# main.net
KiCad netlist of a schematic drawn in EAGLE
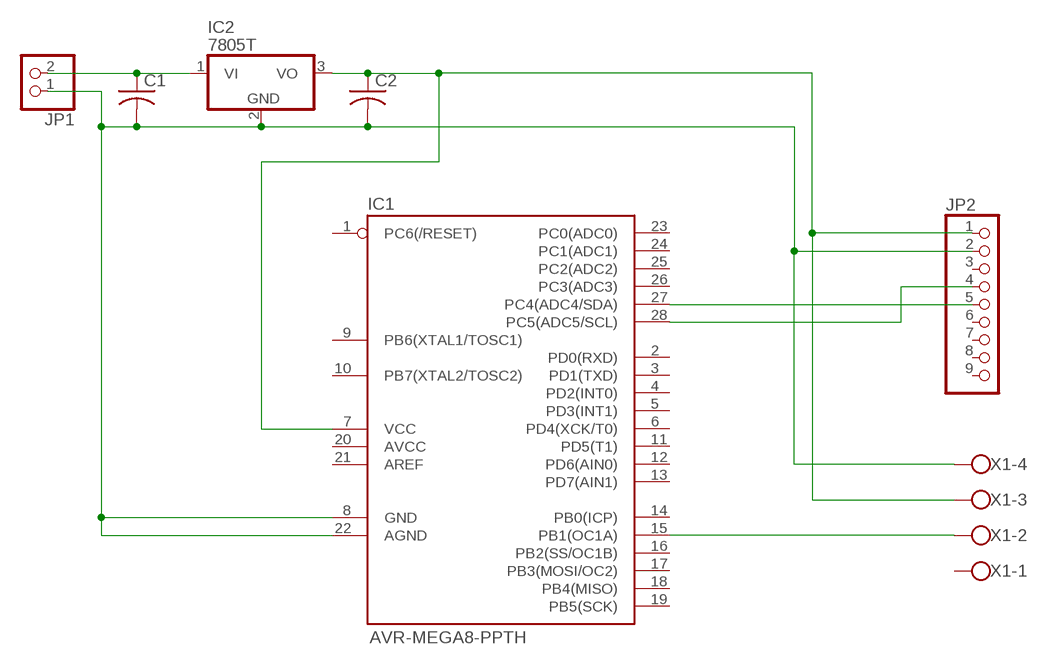
[diagram p0: schematic, sheet 1]

(export (version "E")
  (design (tool "Eeschema 10.0.6"))
  (components
    (comp (ref "C1")
      (value "C-US050-075X075")
      (footprint "eagle-import:C050-075X075")
      (libsource (lib "eagle-import") (part "C-US050-075X075"))
    )
    (comp (ref "C2")
      (value "C-US025-050X050")
      (footprint "eagle-import:C025-050X050")
      (libsource (lib "eagle-import") (part "C-US025-050X050"))
    )
    (comp (ref "IC1")
      (value "AVR-MEGA8-PPTH")
      (footprint "eagle-import:DIL28-3")
      (libsource (lib "eagle-import") (part "AVR-MEGA8-PPTH"))
    )
    (comp (ref "IC2")
      (value "7805T")
      (footprint "eagle-import:TO220H")
      (libsource (lib "eagle-import") (part "78T05"))
    )
    (comp (ref "JP1")
      (value "PINHD-1X2")
      (footprint "eagle-import:1X02")
      (libsource (lib "eagle-import") (part "PINHD-1X2"))
    )
    (comp (ref "JP2")
      (value "PINHD-1X9")
      (footprint "eagle-import:1X09")
      (libsource (lib "eagle-import") (part "PINHD-1X9"))
    )
    (comp (ref "X1")
      (value "W237-4")
      (footprint "eagle-import:W237-4")
      (libsource (lib "eagle-import") (part "W237-4"))
    )
  )
  (nets
    (net (code "1") (name "Net-(IC1-AGND)") (class "Default")
      (node (ref "C1") (pin "2") (pinfunction "2_2") (pintype "passive"))
      (node (ref "C2") (pin "2") (pinfunction "2_2") (pintype "passive"))
      (node (ref "IC1") (pin "22") (pinfunction "AGND_22") (pintype "bidirectional"))
      (node (ref "IC1") (pin "8") (pinfunction "GND_8") (pintype "bidirectional"))
      (node (ref "IC2") (pin "2") (pinfunction "GND_2") (pintype "passive"))
      (node (ref "JP1") (pin "1") (pinfunction "1_1") (pintype "passive"))
      (node (ref "JP2") (pin "2") (pinfunction "2_2") (pintype "passive"))
      (node (ref "X1") (pin "4") (pinfunction "KL_4") (pintype "passive"))
    )
    (net (code "2") (name "Net-(IC1-PB1(OC1A))") (class "Default")
      (node (ref "IC1") (pin "15") (pinfunction "PB1(OC1A)_15") (pintype "bidirectional"))
      (node (ref "X1") (pin "2") (pinfunction "KL_2") (pintype "passive"))
    )
    (net (code "3") (name "Net-(IC1-PC4(ADC4{slash}SDA))") (class "Default")
      (node (ref "IC1") (pin "27") (pinfunction "PC4(ADC4/SDA)_27") (pintype "bidirectional"))
      (node (ref "JP2") (pin "5") (pinfunction "5_5") (pintype "passive"))
    )
    (net (code "4") (name "Net-(IC1-PC5(ADC5{slash}SCL))") (class "Default")
      (node (ref "IC1") (pin "28") (pinfunction "PC5(ADC5/SCL)_28") (pintype "bidirectional"))
      (node (ref "JP2") (pin "4") (pinfunction "4_4") (pintype "passive"))
    )
    (net (code "5") (name "Net-(IC1-VCC)") (class "Default")
      (node (ref "C2") (pin "1") (pinfunction "1_1") (pintype "passive"))
      (node (ref "IC1") (pin "7") (pinfunction "VCC_7") (pintype "bidirectional"))
      (node (ref "IC2") (pin "3") (pinfunction "VO_3") (pintype "passive"))
      (node (ref "JP2") (pin "1") (pinfunction "1_1") (pintype "passive"))
      (node (ref "X1") (pin "3") (pinfunction "KL_3") (pintype "passive"))
    )
    (net (code "6") (name "Net-(IC2-VI)") (class "Default")
      (node (ref "C1") (pin "1") (pinfunction "1_1") (pintype "passive"))
      (node (ref "IC2") (pin "1") (pinfunction "VI_1") (pintype "input"))
      (node (ref "JP1") (pin "2") (pinfunction "2_2") (pintype "passive"))
    )
    (net (code "7") (name "unconnected-(IC1-AREF-Pad21)") (class "Default")
      (node (ref "IC1") (pin "21") (pinfunction "AREF_21") (pintype "bidirectional"))
    )
    (net (code "8") (name "unconnected-(IC1-AVCC-Pad20)") (class "Default")
      (node (ref "IC1") (pin "20") (pinfunction "AVCC_20") (pintype "bidirectional"))
    )
    (net (code "9") (name "unconnected-(IC1-PB0(ICP)-Pad14)") (class "Default")
      (node (ref "IC1") (pin "14") (pinfunction "PB0(ICP)_14") (pintype "bidirectional"))
    )
    (net (code "10") (name "unconnected-(IC1-PB2(SS{slash}OC1B)-Pad16)") (class "Default")
      (node (ref "IC1") (pin "16") (pinfunction "PB2(SS/OC1B)_16") (pintype "bidirectional"))
    )
    (net (code "11") (name "unconnected-(IC1-PB3(MOSI{slash}OC2)-Pad17)") (class "Default")
      (node (ref "IC1") (pin "17") (pinfunction "PB3(MOSI/OC2)_17") (pintype "bidirectional"))
    )
    (net (code "12") (name "unconnected-(IC1-PB4(MISO)-Pad18)") (class "Default")
      (node (ref "IC1") (pin "18") (pinfunction "PB4(MISO)_18") (pintype "bidirectional"))
    )
    (net (code "13") (name "unconnected-(IC1-PB5(SCK)-Pad19)") (class "Default")
      (node (ref "IC1") (pin "19") (pinfunction "PB5(SCK)_19") (pintype "bidirectional"))
    )
    (net (code "14") (name "unconnected-(IC1-PB6(XTAL1{slash}TOSC1)-Pad9)") (class "Default")
      (node (ref "IC1") (pin "9") (pinfunction "PB6(XTAL1/TOSC1)_9") (pintype "bidirectional"))
    )
    (net (code "15") (name "unconnected-(IC1-PB7(XTAL2{slash}TOSC2)-Pad10)") (class "Default")
      (node (ref "IC1") (pin "10") (pinfunction "PB7(XTAL2/TOSC2)_10") (pintype "bidirectional"))
    )
    (net (code "16") (name "unconnected-(IC1-PC0(ADC0)-Pad23)") (class "Default")
      (node (ref "IC1") (pin "23") (pinfunction "PC0(ADC0)_23") (pintype "bidirectional"))
    )
    (net (code "17") (name "unconnected-(IC1-PC1(ADC1)-Pad24)") (class "Default")
      (node (ref "IC1") (pin "24") (pinfunction "PC1(ADC1)_24") (pintype "bidirectional"))
    )
    (net (code "18") (name "unconnected-(IC1-PC2(ADC2)-Pad25)") (class "Default")
      (node (ref "IC1") (pin "25") (pinfunction "PC2(ADC2)_25") (pintype "bidirectional"))
    )
    (net (code "19") (name "unconnected-(IC1-PC3(ADC3)-Pad26)") (class "Default")
      (node (ref "IC1") (pin "26") (pinfunction "PC3(ADC3)_26") (pintype "bidirectional"))
    )
    (net (code "20") (name "unconnected-(IC1-PC6({slash}RESET)-Pad1)") (class "Default")
      (node (ref "IC1") (pin "1") (pinfunction "PC6(/RESET)_1") (pintype "bidirectional"))
    )
    (net (code "21") (name "unconnected-(IC1-PD0(RXD)-Pad2)") (class "Default")
      (node (ref "IC1") (pin "2") (pinfunction "PD0(RXD)_2") (pintype "bidirectional"))
    )
    (net (code "22") (name "unconnected-(IC1-PD1(TXD)-Pad3)") (class "Default")
      (node (ref "IC1") (pin "3") (pinfunction "PD1(TXD)_3") (pintype "bidirectional"))
    )
    (net (code "23") (name "unconnected-(IC1-PD2(INT0)-Pad4)") (class "Default")
      (node (ref "IC1") (pin "4") (pinfunction "PD2(INT0)_4") (pintype "bidirectional"))
    )
    (net (code "24") (name "unconnected-(IC1-PD3(INT1)-Pad5)") (class "Default")
      (node (ref "IC1") (pin "5") (pinfunction "PD3(INT1)_5") (pintype "bidirectional"))
    )
    (net (code "25") (name "unconnected-(IC1-PD4(XCK{slash}T0)-Pad6)") (class "Default")
      (node (ref "IC1") (pin "6") (pinfunction "PD4(XCK/T0)_6") (pintype "bidirectional"))
    )
    (net (code "26") (name "unconnected-(IC1-PD5(T1)-Pad11)") (class "Default")
      (node (ref "IC1") (pin "11") (pinfunction "PD5(T1)_11") (pintype "bidirectional"))
    )
    (net (code "27") (name "unconnected-(IC1-PD6(AIN0)-Pad12)") (class "Default")
      (node (ref "IC1") (pin "12") (pinfunction "PD6(AIN0)_12") (pintype "bidirectional"))
    )
    (net (code "28") (name "unconnected-(IC1-PD7(AIN1)-Pad13)") (class "Default")
      (node (ref "IC1") (pin "13") (pinfunction "PD7(AIN1)_13") (pintype "bidirectional"))
    )
    (net (code "29") (name "unconnected-(JP2-Pad3)") (class "Default")
      (node (ref "JP2") (pin "3") (pinfunction "3_3") (pintype "passive"))
    )
    (net (code "30") (name "unconnected-(JP2-Pad6)") (class "Default")
      (node (ref "JP2") (pin "6") (pinfunction "6_6") (pintype "passive"))
    )
    (net (code "31") (name "unconnected-(JP2-Pad7)") (class "Default")
      (node (ref "JP2") (pin "7") (pinfunction "7_7") (pintype "passive"))
    )
    (net (code "32") (name "unconnected-(JP2-Pad8)") (class "Default")
      (node (ref "JP2") (pin "8") (pinfunction "8_8") (pintype "passive"))
    )
    (net (code "33") (name "unconnected-(JP2-Pad9)") (class "Default")
      (node (ref "JP2") (pin "9") (pinfunction "9_9") (pintype "passive"))
    )
    (net (code "34") (name "unconnected-(X1A-KL-Pad1)") (class "Default")
      (node (ref "X1") (pin "1") (pinfunction "KL_1") (pintype "passive"))
    )
  )
)
